# Supply.net
KiCad netlist of a schematic drawn in Altium Designer
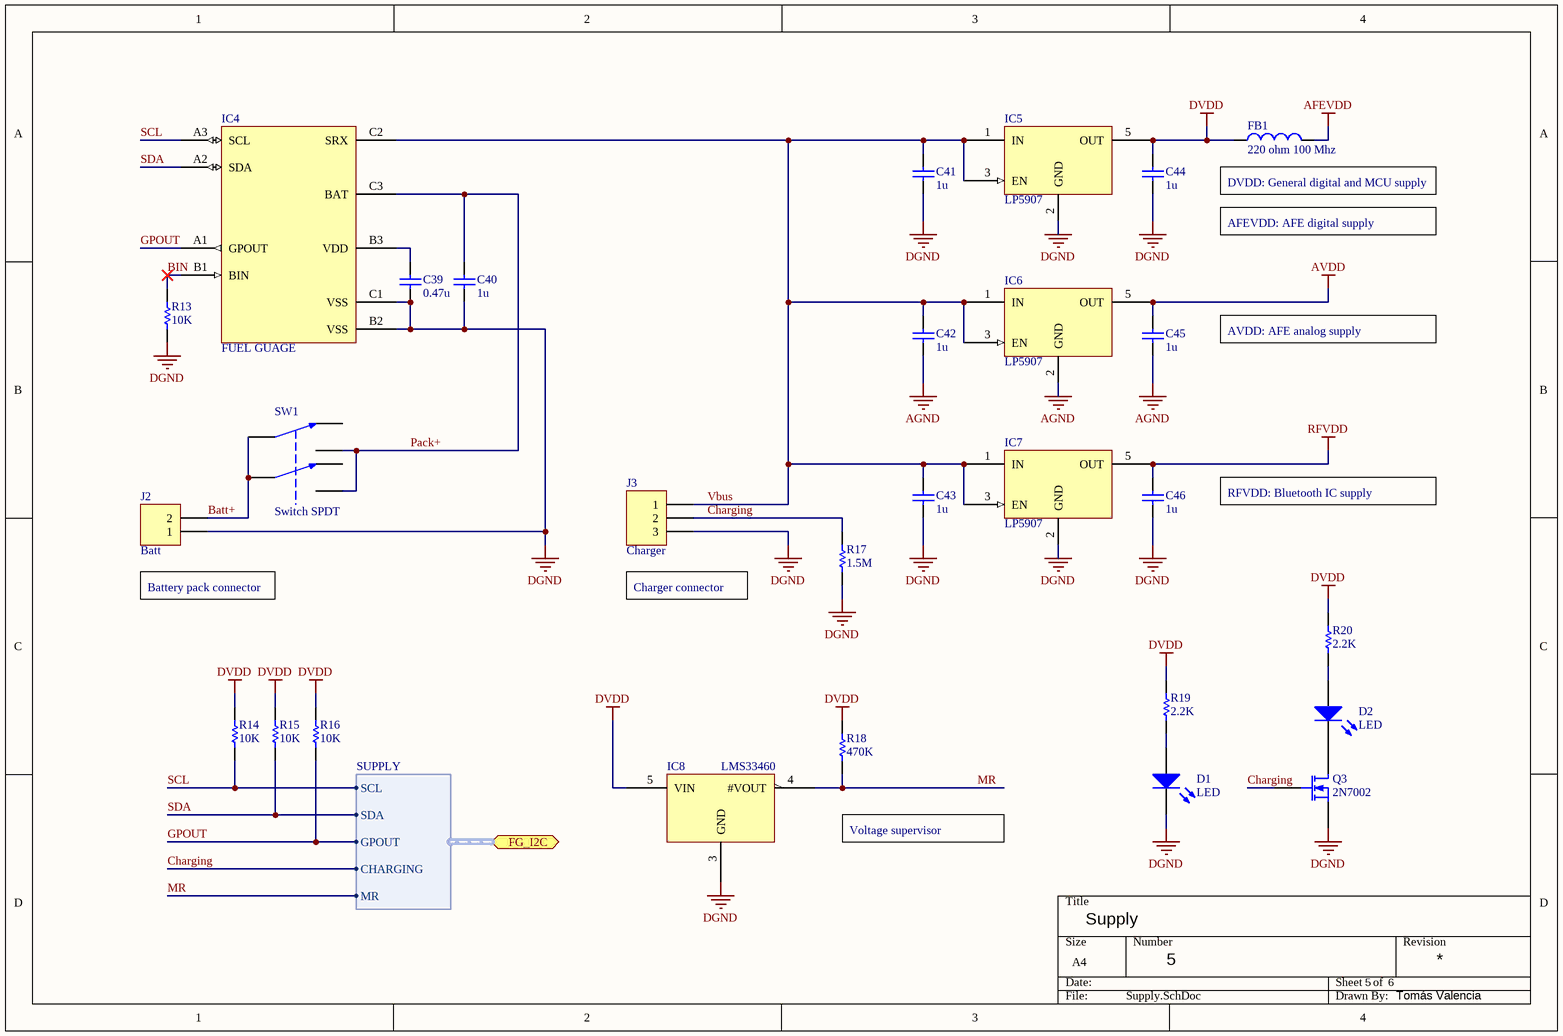
[diagram p0: Supply.SchDoc]

(export (version "E")
  (design (tool "Eeschema 10.0.6"))
  (components
    (comp (ref "C39")
      (value "0.47u")
      (footprint "C0603")
      (description "Capacitor")
      (libsource (lib "Common Devices") (part "Capacitor"))
    )
    (comp (ref "C40")
      (value "1u")
      (footprint "C0603")
      (description "Capacitor")
      (libsource (lib "Common Devices") (part "Capacitor"))
    )
    (comp (ref "C41")
      (value "1u")
      (footprint "C0603")
      (description "Capacitor")
      (libsource (lib "Common Devices") (part "Capacitor"))
    )
    (comp (ref "C42")
      (value "1u")
      (footprint "C0603")
      (description "Capacitor")
      (libsource (lib "Common Devices") (part "Capacitor"))
    )
    (comp (ref "C43")
      (value "1u")
      (footprint "C0603")
      (description "Capacitor")
      (libsource (lib "Common Devices") (part "Capacitor"))
    )
    (comp (ref "C44")
      (value "1u")
      (footprint "C0603")
      (description "Capacitor")
      (libsource (lib "Common Devices") (part "Capacitor"))
    )
    (comp (ref "C45")
      (value "1u")
      (footprint "C0603")
      (description "Capacitor")
      (libsource (lib "Common Devices") (part "Capacitor"))
    )
    (comp (ref "C46")
      (value "1u")
      (footprint "C0603")
      (description "Capacitor")
      (libsource (lib "Common Devices") (part "Capacitor"))
    )
    (comp (ref "D1") (value "LED") (footprint "LED3015M") (libsource (lib "Common Devices") (part "LED")))
    (comp (ref "D2") (value "LED") (footprint "LED3015M") (libsource (lib "Common Devices") (part "LED")))
    (comp (ref "FB1")
      (value "220 ohm 100 Mhz")
      (footprint "0805 Ind")
      (description "INDUCTOR, 0.04OHM, 3A, 0805")
      (libsource (lib "Main Board") (part "Ferrita"))
    )
    (comp (ref "IC4")
      (value "FUEL GUAGE")
      (footprint "BQ27421")
      (libsource (lib "Main Board") (part "BQ27421"))
    )
    (comp (ref "IC5") (value "LP5907") (footprint "SOT23") (libsource (lib "Main Board") (part "LP5907")))
    (comp (ref "IC6") (value "LP5907") (footprint "SOT23") (libsource (lib "Main Board") (part "LP5907")))
    (comp (ref "IC7") (value "LP5907") (footprint "SOT23") (libsource (lib "Main Board") (part "LP5907")))
    (comp (ref "IC8")
      (value "LMS33460")
      (footprint "LMS33460")
      (libsource (lib "Main Board") (part "LMS33460"))
    )
    (comp (ref "J2")
      (value "Batt")
      (footprint "JST PH 2 Socket")
      (description "JST PH 2 Pin Socket")
      (libsource (lib "Common Devices") (part "JST PH 2 Pin Socket"))
    )
    (comp (ref "J3")
      (value "Charger")
      (footprint "JST PH 3 Socket")
      (description "JST PH 3 Pin Socket")
      (libsource (lib "Common Devices") (part "JST PH 3 Pin Socket"))
    )
    (comp (ref "Q3")
      (value "2N7002")
      (footprint "SOT65P210X110-3N")
      (description "Transistor, MOSFET, N-Channel, 60V, 300mA")
      (libsource (lib "Common Devices") (part "2N7002"))
    )
    (comp (ref "R13")
      (value "10K")
      (footprint "R0603")
      (description "Resistor")
      (libsource (lib "Common Devices") (part "Resistor"))
    )
    (comp (ref "R14")
      (value "10K")
      (footprint "R0603")
      (description "Resistor")
      (libsource (lib "Common Devices") (part "Resistor"))
    )
    (comp (ref "R15")
      (value "10K")
      (footprint "R0603")
      (description "Resistor")
      (libsource (lib "Common Devices") (part "Resistor"))
    )
    (comp (ref "R16")
      (value "10K")
      (footprint "R0603")
      (description "Resistor")
      (libsource (lib "Common Devices") (part "Resistor"))
    )
    (comp (ref "R17")
      (value "1.5M")
      (footprint "R0603")
      (description "Resistor")
      (libsource (lib "Common Devices") (part "Resistor"))
    )
    (comp (ref "R18")
      (value "470K")
      (footprint "R0603")
      (description "Resistor")
      (libsource (lib "Common Devices") (part "Resistor"))
    )
    (comp (ref "R19")
      (value "2.2K")
      (footprint "R0603")
      (description "Resistor")
      (libsource (lib "Common Devices") (part "Resistor"))
    )
    (comp (ref "R20")
      (value "2.2K")
      (footprint "R0603")
      (description "Resistor")
      (libsource (lib "Common Devices") (part "Resistor"))
    )
    (comp (ref "SW1")
      (value "Switch SPDT")
      (footprint "MFS201N-16-Z")
      (libsource (lib "Main Board") (part "MFS201N-16-Z"))
    )
  )
  (nets
    (net (code "2") (name "/BIN") (class "Default")
      (node (ref "IC4") (pin "B1") (pinfunction "BIN_B1") (pintype "input"))
      (node (ref "R13") (pin "2") (pinfunction "2_2") (pintype "passive"))
    )
    (net (code "3") (name "/Batt+") (class "Default")
      (node (ref "J2") (pin "2") (pinfunction "2_2") (pintype "passive"))
      (node (ref "SW1") (pin "2") (pinfunction "2_2") (pintype "passive"))
      (node (ref "SW1") (pin "5") (pinfunction "5_5") (pintype "passive"))
    )
    (net (code "4") (name "/Charging") (class "Default")
      (node (ref "J3") (pin "2") (pinfunction "2_2") (pintype "passive"))
      (node (ref "Q3") (pin "1") (pinfunction "G_1") (pintype "passive"))
      (node (ref "R17") (pin "2") (pinfunction "2_2") (pintype "passive"))
    )
    (net (code "5") (name "/GPOUT") (class "Default")
      (node (ref "IC4") (pin "A1") (pinfunction "GPOUT_A1") (pintype "output"))
      (node (ref "R16") (pin "1") (pinfunction "1_1") (pintype "passive"))
    )
    (net (code "6") (name "/MR") (class "Default")
      (node (ref "IC8") (pin "4") (pinfunction "#VOUT_4") (pintype "open_collector"))
      (node (ref "R18") (pin "1") (pinfunction "1_1") (pintype "passive"))
    )
    (net (code "7") (name "/Pack+") (class "Default")
      (node (ref "C40") (pin "2") (pinfunction "2_2") (pintype "passive"))
      (node (ref "IC4") (pin "C3") (pinfunction "BAT_C3") (pintype "power_in"))
      (node (ref "SW1") (pin "3") (pinfunction "3_3") (pintype "passive"))
      (node (ref "SW1") (pin "6") (pinfunction "6_6") (pintype "passive"))
    )
    (net (code "8") (name "/SCL") (class "Default")
      (node (ref "IC4") (pin "A3") (pinfunction "SCL_A3") (pintype "bidirectional"))
      (node (ref "R14") (pin "1") (pinfunction "1_1") (pintype "passive"))
    )
    (net (code "9") (name "/SDA") (class "Default")
      (node (ref "IC4") (pin "A2") (pinfunction "SDA_A2") (pintype "bidirectional"))
      (node (ref "R15") (pin "1") (pinfunction "1_1") (pintype "passive"))
    )
    (net (code "10") (name "/Vbus") (class "Default")
      (node (ref "C41") (pin "2") (pinfunction "2_2") (pintype "passive"))
      (node (ref "C42") (pin "2") (pinfunction "2_2") (pintype "passive"))
      (node (ref "C43") (pin "2") (pinfunction "2_2") (pintype "passive"))
      (node (ref "IC4") (pin "C2") (pinfunction "SRX_C2") (pintype "power_in"))
      (node (ref "IC5") (pin "1") (pinfunction "IN_1") (pintype "power_in"))
      (node (ref "IC5") (pin "3") (pinfunction "EN_3") (pintype "input"))
      (node (ref "IC6") (pin "1") (pinfunction "IN_1") (pintype "power_in"))
      (node (ref "IC6") (pin "3") (pinfunction "EN_3") (pintype "input"))
      (node (ref "IC7") (pin "1") (pinfunction "IN_1") (pintype "power_in"))
      (node (ref "IC7") (pin "3") (pinfunction "EN_3") (pintype "input"))
      (node (ref "J3") (pin "1") (pinfunction "1_1") (pintype "passive"))
    )
    (net (code "12") (name "AFEVDD") (class "Default")
      (node (ref "FB1") (pin "2") (pinfunction "2_2") (pintype "passive"))
    )
    (net (code "13") (name "AGND") (class "Default")
      (node (ref "C42") (pin "1") (pinfunction "1_1") (pintype "passive"))
      (node (ref "C45") (pin "1") (pinfunction "1_1") (pintype "passive"))
      (node (ref "IC6") (pin "2") (pinfunction "GND_2") (pintype "power_in"))
    )
    (net (code "14") (name "AVDD") (class "Default")
      (node (ref "C45") (pin "2") (pinfunction "2_2") (pintype "passive"))
      (node (ref "IC6") (pin "5") (pinfunction "OUT_5") (pintype "power_in"))
    )
    (net (code "15") (name "DGND") (class "Default")
      (node (ref "C39") (pin "1") (pinfunction "1_1") (pintype "passive"))
      (node (ref "C40") (pin "1") (pinfunction "1_1") (pintype "passive"))
      (node (ref "C41") (pin "1") (pinfunction "1_1") (pintype "passive"))
      (node (ref "C43") (pin "1") (pinfunction "1_1") (pintype "passive"))
      (node (ref "C44") (pin "1") (pinfunction "1_1") (pintype "passive"))
      (node (ref "C46") (pin "1") (pinfunction "1_1") (pintype "passive"))
      (node (ref "D1") (pin "2") (pinfunction "K_2") (pintype "passive"))
      (node (ref "IC4") (pin "B2") (pinfunction "VSS_B2") (pintype "power_in"))
      (node (ref "IC4") (pin "C1") (pinfunction "VSS_C1") (pintype "power_in"))
      (node (ref "IC5") (pin "2") (pinfunction "GND_2") (pintype "power_in"))
      (node (ref "IC7") (pin "2") (pinfunction "GND_2") (pintype "power_in"))
      (node (ref "IC8") (pin "3") (pinfunction "GND_3") (pintype "power_in"))
      (node (ref "J2") (pin "1") (pinfunction "1_1") (pintype "passive"))
      (node (ref "J3") (pin "3") (pinfunction "3_3") (pintype "passive"))
      (node (ref "Q3") (pin "2") (pinfunction "S_2") (pintype "passive"))
      (node (ref "R13") (pin "1") (pinfunction "1_1") (pintype "passive"))
      (node (ref "R17") (pin "1") (pinfunction "1_1") (pintype "passive"))
    )
    (net (code "16") (name "DVDD") (class "Default")
      (node (ref "C44") (pin "2") (pinfunction "2_2") (pintype "passive"))
      (node (ref "FB1") (pin "1") (pinfunction "1_1") (pintype "passive"))
      (node (ref "IC5") (pin "5") (pinfunction "OUT_5") (pintype "power_in"))
      (node (ref "IC8") (pin "5") (pinfunction "VIN_5") (pintype "power_in"))
      (node (ref "R14") (pin "2") (pinfunction "2_2") (pintype "passive"))
      (node (ref "R15") (pin "2") (pinfunction "2_2") (pintype "passive"))
      (node (ref "R16") (pin "2") (pinfunction "2_2") (pintype "passive"))
      (node (ref "R18") (pin "2") (pinfunction "2_2") (pintype "passive"))
      (node (ref "R19") (pin "2") (pinfunction "2_2") (pintype "passive"))
      (node (ref "R20") (pin "2") (pinfunction "2_2") (pintype "passive"))
    )
    (net (code "17") (name "Net-(D1-A)") (class "Default")
      (node (ref "D1") (pin "1") (pinfunction "A_1") (pintype "passive"))
      (node (ref "R19") (pin "1") (pinfunction "1_1") (pintype "passive"))
    )
    (net (code "18") (name "Net-(D2-A)") (class "Default")
      (node (ref "D2") (pin "1") (pinfunction "A_1") (pintype "passive"))
      (node (ref "R20") (pin "1") (pinfunction "1_1") (pintype "passive"))
    )
    (net (code "19") (name "Net-(D2-K)") (class "Default")
      (node (ref "D2") (pin "2") (pinfunction "K_2") (pintype "passive"))
      (node (ref "Q3") (pin "3") (pinfunction "D_3") (pintype "passive"))
    )
    (net (code "20") (name "Net-(IC4-VDD)") (class "Default")
      (node (ref "C39") (pin "2") (pinfunction "2_2") (pintype "passive"))
      (node (ref "IC4") (pin "B3") (pinfunction "VDD_B3") (pintype "power_in"))
    )
    (net (code "21") (name "RFVDD") (class "Default")
      (node (ref "C46") (pin "2") (pinfunction "2_2") (pintype "passive"))
      (node (ref "IC7") (pin "5") (pinfunction "OUT_5") (pintype "power_in"))
    )
    (net (code "22") (name "unconnected-(SW1-Pad1)") (class "Default")
      (node (ref "SW1") (pin "1") (pinfunction "1_1") (pintype "passive"))
    )
    (net (code "23") (name "unconnected-(SW1-Pad4)") (class "Default")
      (node (ref "SW1") (pin "4") (pinfunction "4_4") (pintype "passive"))
    )
  )
)
